# LoveMeter.net
KiCad netlist of a schematic drawn in EAGLE
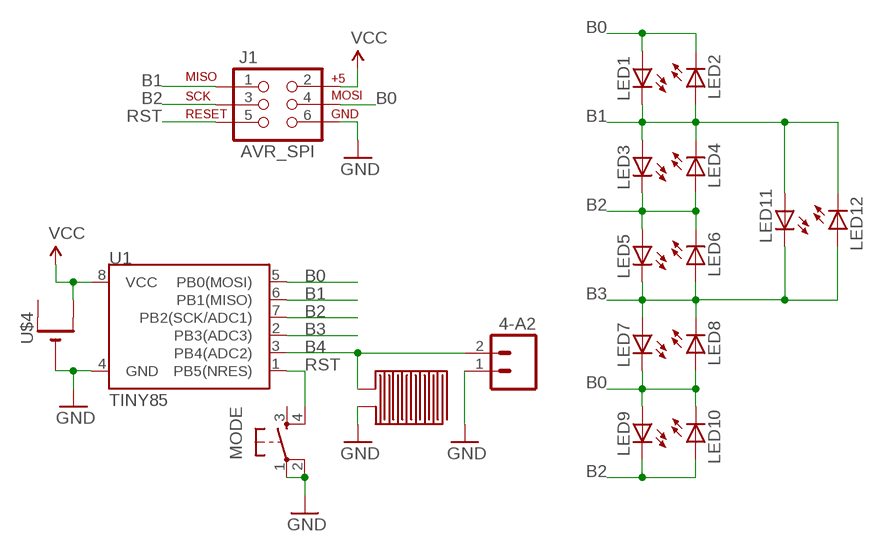
[diagram p0: schematic, sheet 1]

(export (version "E")
  (design (tool "Eeschema 10.0.6"))
  (components
    (comp (ref "4-A2")
      (value "M02PTH")
      (footprint "eagle-import:1X02")
      (libsource (lib "eagle-import") (part "M02PTH"))
    )
    (comp (ref "J1")
      (value "AVR_SPI")
      (footprint "eagle-import:2X3-NS")
      (libsource (lib "eagle-import") (part "AVR_SPI_PRG_6LABELED"))
    )
    (comp (ref "LED1")
      (value "LEDOVAL")
      (footprint "eagle-import:LED-OVAL")
      (libsource (lib "eagle-import") (part "LEDOVAL"))
    )
    (comp (ref "LED2")
      (value "LEDOVAL")
      (footprint "eagle-import:LED-OVAL")
      (libsource (lib "eagle-import") (part "LEDOVAL"))
    )
    (comp (ref "LED3")
      (value "LEDOVAL")
      (footprint "eagle-import:LED-OVAL")
      (libsource (lib "eagle-import") (part "LEDOVAL"))
    )
    (comp (ref "LED4")
      (value "LEDOVAL")
      (footprint "eagle-import:LED-OVAL")
      (libsource (lib "eagle-import") (part "LEDOVAL"))
    )
    (comp (ref "LED5")
      (value "LEDOVAL")
      (footprint "eagle-import:LED-OVAL")
      (libsource (lib "eagle-import") (part "LEDOVAL"))
    )
    (comp (ref "LED6")
      (value "LEDOVAL")
      (footprint "eagle-import:LED-OVAL")
      (libsource (lib "eagle-import") (part "LEDOVAL"))
    )
    (comp (ref "LED7")
      (value "LEDOVAL")
      (footprint "eagle-import:LED-OVAL")
      (libsource (lib "eagle-import") (part "LEDOVAL"))
    )
    (comp (ref "LED8")
      (value "LEDOVAL")
      (footprint "eagle-import:LED-OVAL")
      (libsource (lib "eagle-import") (part "LEDOVAL"))
    )
    (comp (ref "LED9")
      (value "LEDOVAL")
      (footprint "eagle-import:LED-OVAL")
      (libsource (lib "eagle-import") (part "LEDOVAL"))
    )
    (comp (ref "LED10")
      (value "LEDOVAL")
      (footprint "eagle-import:LED-OVAL")
      (libsource (lib "eagle-import") (part "LEDOVAL"))
    )
    (comp (ref "LED11")
      (value "LEDOVAL")
      (footprint "eagle-import:LED-OVAL")
      (libsource (lib "eagle-import") (part "LEDOVAL"))
    )
    (comp (ref "LED12")
      (value "LEDOVAL")
      (footprint "eagle-import:LED-OVAL")
      (libsource (lib "eagle-import") (part "LEDOVAL"))
    )
    (comp (ref "MODE")
      (value "TAC_SWITCHPTH")
      (footprint "eagle-import:TACTILE-PTH")
      (libsource (lib "eagle-import") (part "TAC_SWITCHPTH"))
    )
    (comp (ref "U$3")
      (value "THUMB_PAD")
      (footprint "eagle-import:THUMB_PAD")
      (libsource (lib "eagle-import") (part "THUMB_PAD"))
    )
    (comp (ref "U$4")
      (value "CR2032STRAP")
      (footprint "eagle-import:CR2032_STRAP")
      (libsource (lib "eagle-import") (part "CR2032STRAP"))
    )
    (comp (ref "U1")
      (value "TINY85")
      (footprint "eagle-import:DIP08")
      (libsource (lib "eagle-import") (part "ATTINY45TINY85-20-DIP"))
    )
  )
  (nets
    (net (code "1") (name "/B0") (class "Default")
      (node (ref "J1") (pin "4") (pinfunction "MOSI_4") (pintype "passive"))
      (node (ref "LED1") (pin "ANODE") (pinfunction "A_ANODE") (pintype "passive"))
      (node (ref "LED10") (pin "CATHODE") (pinfunction "C_CATHODE") (pintype "passive"))
      (node (ref "LED2") (pin "CATHODE") (pinfunction "C_CATHODE") (pintype "passive"))
      (node (ref "LED7") (pin "CATHODE") (pinfunction "C_CATHODE") (pintype "passive"))
      (node (ref "LED8") (pin "ANODE") (pinfunction "A_ANODE") (pintype "passive"))
      (node (ref "LED9") (pin "ANODE") (pinfunction "A_ANODE") (pintype "passive"))
      (node (ref "U1") (pin "5") (pinfunction "PB0(MOSI)_5") (pintype "bidirectional"))
    )
    (net (code "2") (name "/B1") (class "Default")
      (node (ref "J1") (pin "1") (pinfunction "MISO_1") (pintype "passive"))
      (node (ref "LED1") (pin "CATHODE") (pinfunction "C_CATHODE") (pintype "passive"))
      (node (ref "LED11") (pin "ANODE") (pinfunction "A_ANODE") (pintype "passive"))
      (node (ref "LED12") (pin "CATHODE") (pinfunction "C_CATHODE") (pintype "passive"))
      (node (ref "LED2") (pin "ANODE") (pinfunction "A_ANODE") (pintype "passive"))
      (node (ref "LED3") (pin "ANODE") (pinfunction "A_ANODE") (pintype "passive"))
      (node (ref "LED4") (pin "CATHODE") (pinfunction "C_CATHODE") (pintype "passive"))
      (node (ref "U1") (pin "6") (pinfunction "PB1(MISO)_6") (pintype "bidirectional"))
    )
    (net (code "3") (name "/B2") (class "Default")
      (node (ref "J1") (pin "3") (pinfunction "SCK_3") (pintype "passive"))
      (node (ref "LED10") (pin "ANODE") (pinfunction "A_ANODE") (pintype "passive"))
      (node (ref "LED3") (pin "CATHODE") (pinfunction "C_CATHODE") (pintype "passive"))
      (node (ref "LED4") (pin "ANODE") (pinfunction "A_ANODE") (pintype "passive"))
      (node (ref "LED5") (pin "ANODE") (pinfunction "A_ANODE") (pintype "passive"))
      (node (ref "LED6") (pin "CATHODE") (pinfunction "C_CATHODE") (pintype "passive"))
      (node (ref "LED9") (pin "CATHODE") (pinfunction "C_CATHODE") (pintype "passive"))
      (node (ref "U1") (pin "7") (pinfunction "PB2(SCK/ADC1)_7") (pintype "bidirectional"))
    )
    (net (code "4") (name "/B3") (class "Default")
      (node (ref "LED11") (pin "CATHODE") (pinfunction "C_CATHODE") (pintype "passive"))
      (node (ref "LED12") (pin "ANODE") (pinfunction "A_ANODE") (pintype "passive"))
      (node (ref "LED5") (pin "CATHODE") (pinfunction "C_CATHODE") (pintype "passive"))
      (node (ref "LED6") (pin "ANODE") (pinfunction "A_ANODE") (pintype "passive"))
      (node (ref "LED7") (pin "ANODE") (pinfunction "A_ANODE") (pintype "passive"))
      (node (ref "LED8") (pin "CATHODE") (pinfunction "C_CATHODE") (pintype "passive"))
      (node (ref "U1") (pin "2") (pinfunction "PB3(ADC3)_2") (pintype "bidirectional"))
    )
    (net (code "5") (name "/B4") (class "Default")
      (node (ref "4-A2") (pin "2") (pinfunction "2_2") (pintype "passive"))
      (node (ref "U$3") (pin "2") (pinfunction "2_2") (pintype "bidirectional"))
      (node (ref "U1") (pin "3") (pinfunction "PB4(ADC2)_3") (pintype "bidirectional"))
    )
    (net (code "6") (name "/RST") (class "Default")
      (node (ref "J1") (pin "5") (pinfunction "RST_5") (pintype "passive"))
      (node (ref "MODE") (pin "4") (pinfunction "4_4") (pintype "passive"))
      (node (ref "U1") (pin "1") (pinfunction "PB5(NRES)_1") (pintype "bidirectional"))
    )
    (net (code "7") (name "GND") (class "Default")
      (node (ref "4-A2") (pin "1") (pinfunction "1_1") (pintype "passive"))
      (node (ref "J1") (pin "6") (pinfunction "GND_6") (pintype "passive"))
      (node (ref "MODE") (pin "1") (pinfunction "1_1") (pintype "passive"))
      (node (ref "MODE") (pin "2") (pinfunction "2_2") (pintype "passive"))
      (node (ref "U$3") (pin "1") (pinfunction "1_1") (pintype "bidirectional"))
      (node (ref "U$4") (pin "-") (pinfunction "-_-") (pintype "passive"))
      (node (ref "U1") (pin "4") (pinfunction "GND_4") (pintype "bidirectional"))
    )
    (net (code "8") (name "VCC") (class "Default")
      (node (ref "J1") (pin "2") (pinfunction "V+_2") (pintype "passive"))
      (node (ref "U$4") (pin "+2") (pinfunction "+1_+2") (pintype "passive"))
      (node (ref "U1") (pin "8") (pinfunction "VCC_8") (pintype "bidirectional"))
    )
    (net (code "9") (name "unconnected-(MODE-Pad3)") (class "Default")
      (node (ref "MODE") (pin "3") (pinfunction "3_3") (pintype "passive"))
    )
    (net (code "10") (name "unconnected-(U$4-Pad+)") (class "Default")
      (node (ref "U$4") (pin "+") (pinfunction "+_+") (pintype "passive"))
    )
  )
)
